# Sheet.net
KiCad netlist of a schematic drawn in Altium Designer
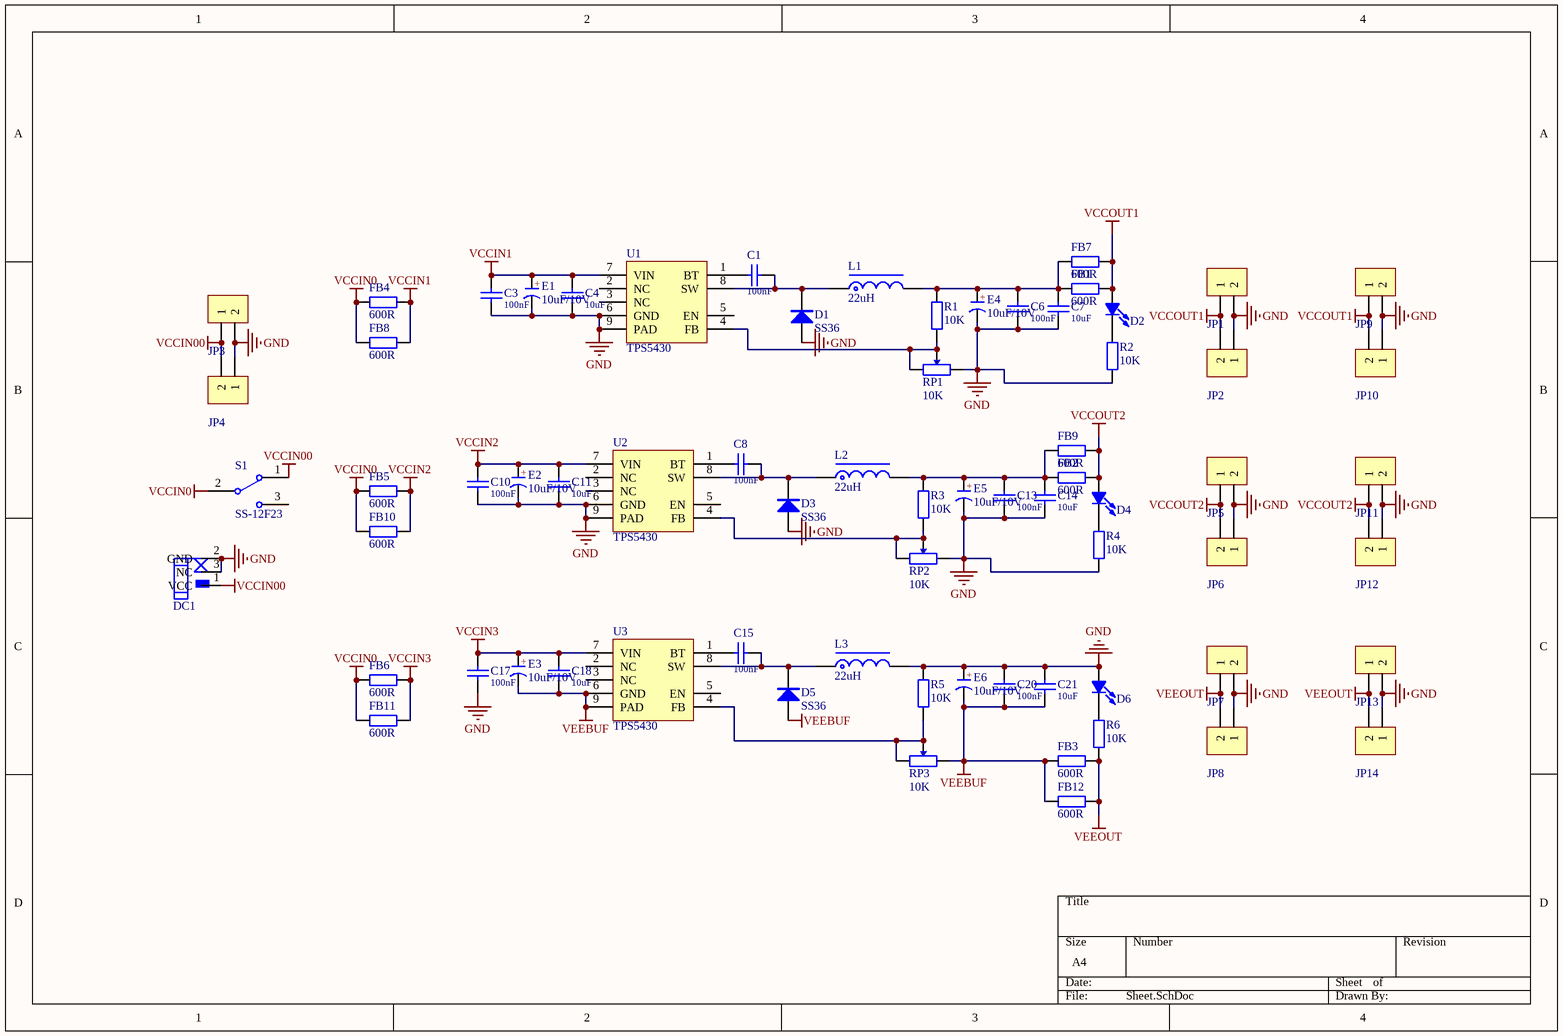
[diagram p0: Sheet.SchDoc]

(export (version "E")
  (design (tool "Eeschema 10.0.6"))
  (components
    (comp (ref "C1")
      (value "100nF")
      (footprint "C0603-L")
      (description "贴片瓷片电容")
      (fields (field (name "Comment") "Cap-S"))
      (libsource (lib "Library") (part "Cap-S"))
    )
    (comp (ref "C3")
      (value "100nF")
      (footprint "C0603-L")
      (description "贴片瓷片电容")
      (fields (field (name "Comment") "Cap-S"))
      (libsource (lib "Library") (part "Cap-S"))
    )
    (comp (ref "C4")
      (value "10uF")
      (footprint "C0603-L")
      (description "贴片瓷片电容")
      (fields (field (name "Comment") "Cap-S"))
      (libsource (lib "Library") (part "Cap-S"))
    )
    (comp (ref "C6")
      (value "100nF")
      (footprint "C0603-L")
      (description "贴片瓷片电容")
      (fields (field (name "Comment") "Cap-S"))
      (libsource (lib "Library") (part "Cap-S"))
    )
    (comp (ref "C7")
      (value "10uF")
      (footprint "C0603-L")
      (description "贴片瓷片电容")
      (fields (field (name "Comment") "Cap-S"))
      (libsource (lib "Library") (part "Cap-S"))
    )
    (comp (ref "C8")
      (value "100nF")
      (footprint "C0603-L")
      (description "贴片瓷片电容")
      (fields (field (name "Comment") "Cap-S"))
      (libsource (lib "Library") (part "Cap-S"))
    )
    (comp (ref "C10")
      (value "100nF")
      (footprint "C0603-L")
      (description "贴片瓷片电容")
      (fields (field (name "Comment") "Cap-S"))
      (libsource (lib "Library") (part "Cap-S"))
    )
    (comp (ref "C11")
      (value "10uF")
      (footprint "C0603-L")
      (description "贴片瓷片电容")
      (fields (field (name "Comment") "Cap-S"))
      (libsource (lib "Library") (part "Cap-S"))
    )
    (comp (ref "C13")
      (value "100nF")
      (footprint "C0603-L")
      (description "贴片瓷片电容")
      (fields (field (name "Comment") "Cap-S"))
      (libsource (lib "Library") (part "Cap-S"))
    )
    (comp (ref "C14")
      (value "10uF")
      (footprint "C0603-L")
      (description "贴片瓷片电容")
      (fields (field (name "Comment") "Cap-S"))
      (libsource (lib "Library") (part "Cap-S"))
    )
    (comp (ref "C15")
      (value "100nF")
      (footprint "C0603-L")
      (description "贴片瓷片电容")
      (fields (field (name "Comment") "Cap-S"))
      (libsource (lib "Library") (part "Cap-S"))
    )
    (comp (ref "C17")
      (value "100nF")
      (footprint "C0603-L")
      (description "贴片瓷片电容")
      (fields (field (name "Comment") "Cap-S"))
      (libsource (lib "Library") (part "Cap-S"))
    )
    (comp (ref "C18")
      (value "10uF")
      (footprint "C0603-L")
      (description "贴片瓷片电容")
      (fields (field (name "Comment") "Cap-S"))
      (libsource (lib "Library") (part "Cap-S"))
    )
    (comp (ref "C20")
      (value "100nF")
      (footprint "C0603-L")
      (description "贴片瓷片电容")
      (fields (field (name "Comment") "Cap-S"))
      (libsource (lib "Library") (part "Cap-S"))
    )
    (comp (ref "C21")
      (value "10uF")
      (footprint "C0603-L")
      (description "贴片瓷片电容")
      (fields (field (name "Comment") "Cap-S"))
      (libsource (lib "Library") (part "Cap-S"))
    )
    (comp (ref "D1")
      (value "SS36")
      (footprint "SMA")
      (description "整流二极管")
      (fields (field (name "版权归属") "源创客"))
      (libsource (lib "IL") (part "M7"))
    )
    (comp (ref "D2")
      (value "LED")
      (footprint "Led-0805_L")
      (description "发光二极管")
      (libsource (lib "Library") (part "LED"))
    )
    (comp (ref "D3")
      (value "SS36")
      (footprint "SMA")
      (description "整流二极管")
      (fields (field (name "版权归属") "源创客"))
      (libsource (lib "IL") (part "M7"))
    )
    (comp (ref "D4")
      (value "LED")
      (footprint "Led-0805_L")
      (description "发光二极管")
      (libsource (lib "Library") (part "LED"))
    )
    (comp (ref "D5")
      (value "SS36")
      (footprint "SMA")
      (description "整流二极管")
      (fields (field (name "版权归属") "源创客"))
      (libsource (lib "IL") (part "M7"))
    )
    (comp (ref "D6")
      (value "LED")
      (footprint "Led-0805_L")
      (description "发光二极管")
      (libsource (lib "Library") (part "LED"))
    )
    (comp (ref "DC1")
      (value "DC")
      (footprint "DCIN-L")
      (description "DC插座")
      (libsource (lib "Library") (part "DC"))
    )
    (comp (ref "E1")
      (value "10uF/10V")
      (footprint "CT 6*6 - V")
      (description "贴片固态电容")
      (fields (field (name "版权归属") "源创客"))
      (libsource (lib "IL") (part "C-CT"))
    )
    (comp (ref "E2")
      (value "10uF/10V")
      (footprint "CT 6*6 - V")
      (description "贴片固态电容")
      (fields (field (name "版权归属") "源创客"))
      (libsource (lib "IL") (part "C-CT"))
    )
    (comp (ref "E3")
      (value "10uF/10V")
      (footprint "CT 6*6 - V")
      (description "贴片固态电容")
      (fields (field (name "版权归属") "源创客"))
      (libsource (lib "IL") (part "C-CT"))
    )
    (comp (ref "E4")
      (value "10uF/10V")
      (footprint "CT 6*6 - V")
      (description "贴片固态电容")
      (fields (field (name "版权归属") "源创客"))
      (libsource (lib "IL") (part "C-CT"))
    )
    (comp (ref "E5")
      (value "10uF/10V")
      (footprint "CT 6*6 - V")
      (description "贴片固态电容")
      (fields (field (name "版权归属") "源创客"))
      (libsource (lib "IL") (part "C-CT"))
    )
    (comp (ref "E6")
      (value "10uF/10V")
      (footprint "CT 6*6 - V")
      (description "贴片固态电容")
      (fields (field (name "版权归属") "源创客"))
      (libsource (lib "IL") (part "C-CT"))
    )
    (comp (ref "FB1") (value "600R") (footprint "FB-0603") (libsource (lib "Library") (part "FB")))
    (comp (ref "FB2") (value "600R") (footprint "FB-0603") (libsource (lib "Library") (part "FB")))
    (comp (ref "FB3") (value "600R") (footprint "FB-0603") (libsource (lib "Library") (part "FB")))
    (comp (ref "FB4") (value "600R") (footprint "FB-0603") (libsource (lib "Library") (part "FB")))
    (comp (ref "FB5") (value "600R") (footprint "FB-0603") (libsource (lib "Library") (part "FB")))
    (comp (ref "FB6") (value "600R") (footprint "FB-0603") (libsource (lib "Library") (part "FB")))
    (comp (ref "FB7") (value "600R") (footprint "FB-0603") (libsource (lib "Library") (part "FB")))
    (comp (ref "FB8") (value "600R") (footprint "FB-0603") (libsource (lib "Library") (part "FB")))
    (comp (ref "FB9") (value "600R") (footprint "FB-0603") (libsource (lib "Library") (part "FB")))
    (comp (ref "FB10") (value "600R") (footprint "FB-0603") (libsource (lib "Library") (part "FB")))
    (comp (ref "FB11") (value "600R") (footprint "FB-0603") (libsource (lib "Library") (part "FB")))
    (comp (ref "FB12") (value "600R") (footprint "FB-0603") (libsource (lib "Library") (part "FB")))
    (comp (ref "JP1")
      (value "HDR-1X2")
      (footprint "VH3.96-LI-2P")
      (description "2P接插件")
      (fields (field (name "版权归属") "源创客"))
      (libsource (lib "") (part "Header 2_1_1"))
    )
    (comp (ref "JP2")
      (value "HDR-1X2")
      (footprint "VH3.96-LI-2P")
      (description "2P接插件")
      (fields (field (name "版权归属") "源创客"))
      (libsource (lib "IL") (part "Header 2_1"))
    )
    (comp (ref "JP3")
      (value "HDR-1X2")
      (footprint "VH3.96-LI-2P")
      (description "2P接插件")
      (fields (field (name "版权归属") "源创客"))
      (libsource (lib "") (part "Header 2_1_1"))
    )
    (comp (ref "JP4")
      (value "HDR-1X2")
      (footprint "VH3.96-LI-2P")
      (description "2P接插件")
      (fields (field (name "版权归属") "源创客"))
      (libsource (lib "IL") (part "Header 2_1"))
    )
    (comp (ref "JP5")
      (value "HDR-1X2")
      (footprint "VH3.96-LI-2P")
      (description "2P接插件")
      (fields (field (name "版权归属") "源创客"))
      (libsource (lib "") (part "Header 2_1_1"))
    )
    (comp (ref "JP6")
      (value "HDR-1X2")
      (footprint "VH3.96-LI-2P")
      (description "2P接插件")
      (fields (field (name "版权归属") "源创客"))
      (libsource (lib "IL") (part "Header 2_1"))
    )
    (comp (ref "JP7")
      (value "HDR-1X2")
      (footprint "VH3.96-LI-2P")
      (description "2P接插件")
      (fields (field (name "版权归属") "源创客"))
      (libsource (lib "") (part "Header 2_1_1"))
    )
    (comp (ref "JP8")
      (value "HDR-1X2")
      (footprint "VH3.96-LI-2P")
      (description "2P接插件")
      (fields (field (name "版权归属") "源创客"))
      (libsource (lib "IL") (part "Header 2_1"))
    )
    (comp (ref "JP9")
      (value "HDR-1X2")
      (footprint "VH3.96-LI-2P")
      (description "2P接插件")
      (fields (field (name "版权归属") "源创客"))
      (libsource (lib "") (part "Header 2_1_1"))
    )
    (comp (ref "JP10")
      (value "HDR-1X2")
      (footprint "VH3.96-LI-2P")
      (description "2P接插件")
      (fields (field (name "版权归属") "源创客"))
      (libsource (lib "IL") (part "Header 2_1"))
    )
    (comp (ref "JP11")
      (value "HDR-1X2")
      (footprint "VH3.96-LI-2P")
      (description "2P接插件")
      (fields (field (name "版权归属") "源创客"))
      (libsource (lib "") (part "Header 2_1_1"))
    )
    (comp (ref "JP12")
      (value "HDR-1X2")
      (footprint "VH3.96-LI-2P")
      (description "2P接插件")
      (fields (field (name "版权归属") "源创客"))
      (libsource (lib "IL") (part "Header 2_1"))
    )
    (comp (ref "JP13")
      (value "HDR-1X2")
      (footprint "VH3.96-LI-2P")
      (description "2P接插件")
      (fields (field (name "版权归属") "源创客"))
      (libsource (lib "") (part "Header 2_1_1"))
    )
    (comp (ref "JP14")
      (value "HDR-1X2")
      (footprint "VH3.96-LI-2P")
      (description "2P接插件")
      (fields (field (name "版权归属") "源创客"))
      (libsource (lib "IL") (part "Header 2_1"))
    )
    (comp (ref "L1")
      (value "22uH")
      (footprint "CDRH73")
      (description "功率屏蔽电感")
      (fields (field (name "版权归属") "源创客"))
      (libsource (lib "IL") (part "L-CDRH"))
    )
    (comp (ref "L2")
      (value "22uH")
      (footprint "CDRH73")
      (description "功率屏蔽电感")
      (fields (field (name "版权归属") "源创客"))
      (libsource (lib "IL") (part "L-CDRH"))
    )
    (comp (ref "L3")
      (value "22uH")
      (footprint "CDRH73")
      (description "功率屏蔽电感")
      (fields (field (name "版权归属") "源创客"))
      (libsource (lib "IL") (part "L-CDRH"))
    )
    (comp (ref "R1")
      (value "10K")
      (footprint "R 0603_L")
      (description "贴片电阻")
      (fields (field (name "版权归属") "源创客"))
      (libsource (lib "IL") (part "R"))
    )
    (comp (ref "R2")
      (value "10K")
      (footprint "R 0603_L")
      (description "贴片电阻")
      (fields (field (name "版权归属") "源创客"))
      (libsource (lib "IL") (part "R"))
    )
    (comp (ref "R3")
      (value "10K")
      (footprint "R 0603_L")
      (description "贴片电阻")
      (fields (field (name "版权归属") "源创客"))
      (libsource (lib "IL") (part "R"))
    )
    (comp (ref "R4")
      (value "10K")
      (footprint "R 0603_L")
      (description "贴片电阻")
      (fields (field (name "版权归属") "源创客"))
      (libsource (lib "IL") (part "R"))
    )
    (comp (ref "R5")
      (value "10K")
      (footprint "R 0603_L")
      (description "贴片电阻")
      (fields (field (name "版权归属") "源创客"))
      (libsource (lib "IL") (part "R"))
    )
    (comp (ref "R6")
      (value "10K")
      (footprint "R 0603_L")
      (description "贴片电阻")
      (fields (field (name "版权归属") "源创客"))
      (libsource (lib "IL") (part "R"))
    )
    (comp (ref "RP1")
      (value "10K")
      (footprint "3296W")
      (description "插件单联电位器")
      (fields (field (name "版权归属") "源创客"))
      (libsource (lib "IL") (part "RP-ID"))
    )
    (comp (ref "RP2")
      (value "10K")
      (footprint "3296W")
      (description "插件单联电位器")
      (fields (field (name "版权归属") "源创客"))
      (libsource (lib "IL") (part "RP-ID"))
    )
    (comp (ref "RP3")
      (value "10K")
      (footprint "3296W")
      (description "插件单联电位器")
      (fields (field (name "版权归属") "源创客"))
      (libsource (lib "IL") (part "RP-ID"))
    )
    (comp (ref "S1")
      (value "SS-12F23")
      (footprint "SS-12D10")
      (description "1路波动开关")
      (fields (field (name "版权归属") "源创客"))
      (libsource (lib "IL") (part "SSW-1P"))
    )
    (comp (ref "U1")
      (value "TPS5430")
      (footprint "SOP-8 with pad")
      (libsource (lib "Library") (part "TPS5430"))
    )
    (comp (ref "U2")
      (value "TPS5430")
      (footprint "SOP-8 with pad")
      (libsource (lib "Library") (part "TPS5430"))
    )
    (comp (ref "U3")
      (value "TPS5430")
      (footprint "SOP-8 with pad")
      (libsource (lib "Library") (part "TPS5430"))
    )
  )
  (nets
    (net (code "1") (name "GND") (class "Default")
      (node (ref "C10") (pin "1") (pinfunction "1_1") (pintype "passive"))
      (node (ref "C11") (pin "1") (pinfunction "1_1") (pintype "passive"))
      (node (ref "C13") (pin "1") (pinfunction "1_1") (pintype "passive"))
      (node (ref "C14") (pin "1") (pinfunction "1_1") (pintype "passive"))
      (node (ref "C17") (pin "1") (pinfunction "1_1") (pintype "passive"))
      (node (ref "C20") (pin "2") (pinfunction "2_2") (pintype "passive"))
      (node (ref "C21") (pin "2") (pinfunction "2_2") (pintype "passive"))
      (node (ref "C3") (pin "1") (pinfunction "1_1") (pintype "passive"))
      (node (ref "C4") (pin "1") (pinfunction "1_1") (pintype "passive"))
      (node (ref "C6") (pin "1") (pinfunction "1_1") (pintype "passive"))
      (node (ref "C7") (pin "1") (pinfunction "1_1") (pintype "passive"))
      (node (ref "D1") (pin "1") (pinfunction "A_1") (pintype "passive"))
      (node (ref "D3") (pin "1") (pinfunction "A_1") (pintype "passive"))
      (node (ref "D6") (pin "1") (pinfunction "1_1") (pintype "passive"))
      (node (ref "DC1") (pin "2") (pinfunction "GND_2") (pintype "open_collector"))
      (node (ref "DC1") (pin "3") (pinfunction "NC_3") (pintype "open_collector"))
      (node (ref "E1") (pin "2") (pinfunction "K_2") (pintype "passive"))
      (node (ref "E2") (pin "2") (pinfunction "K_2") (pintype "passive"))
      (node (ref "E4") (pin "2") (pinfunction "K_2") (pintype "passive"))
      (node (ref "E5") (pin "2") (pinfunction "K_2") (pintype "passive"))
      (node (ref "E6") (pin "1") (pinfunction "A_1") (pintype "passive"))
      (node (ref "JP1") (pin "2") (pinfunction "2_2") (pintype "passive"))
      (node (ref "JP10") (pin "1") (pinfunction "1_1") (pintype "passive"))
      (node (ref "JP11") (pin "2") (pinfunction "2_2") (pintype "passive"))
      (node (ref "JP12") (pin "1") (pinfunction "1_1") (pintype "passive"))
      (node (ref "JP13") (pin "2") (pinfunction "2_2") (pintype "passive"))
      (node (ref "JP14") (pin "1") (pinfunction "1_1") (pintype "passive"))
      (node (ref "JP2") (pin "1") (pinfunction "1_1") (pintype "passive"))
      (node (ref "JP3") (pin "2") (pinfunction "2_2") (pintype "passive"))
      (node (ref "JP4") (pin "1") (pinfunction "1_1") (pintype "passive"))
      (node (ref "JP5") (pin "2") (pinfunction "2_2") (pintype "passive"))
      (node (ref "JP6") (pin "1") (pinfunction "1_1") (pintype "passive"))
      (node (ref "JP7") (pin "2") (pinfunction "2_2") (pintype "passive"))
      (node (ref "JP8") (pin "1") (pinfunction "1_1") (pintype "passive"))
      (node (ref "JP9") (pin "2") (pinfunction "2_2") (pintype "passive"))
      (node (ref "L3") (pin "2") (pinfunction "2_2") (pintype "passive"))
      (node (ref "R2") (pin "1") (pinfunction "1_1") (pintype "passive"))
      (node (ref "R4") (pin "1") (pinfunction "1_1") (pintype "passive"))
      (node (ref "R5") (pin "2") (pinfunction "2_2") (pintype "passive"))
      (node (ref "RP1") (pin "3") (pinfunction "3_3") (pintype "passive"))
      (node (ref "RP2") (pin "3") (pinfunction "3_3") (pintype "passive"))
      (node (ref "U1") (pin "6") (pinfunction "GND_6") (pintype "passive"))
      (node (ref "U1") (pin "9") (pinfunction "PAD_9") (pintype "passive"))
      (node (ref "U2") (pin "6") (pinfunction "GND_6") (pintype "passive"))
      (node (ref "U2") (pin "9") (pinfunction "PAD_9") (pintype "passive"))
    )
    (net (code "2") (name "Net-(D1-K)") (class "Default")
      (node (ref "C1") (pin "2") (pinfunction "2_2") (pintype "passive"))
      (node (ref "D1") (pin "2") (pinfunction "K_2") (pintype "passive"))
      (node (ref "L1") (pin "1") (pinfunction "1_1") (pintype "passive"))
      (node (ref "U1") (pin "8") (pinfunction "SW_8") (pintype "passive"))
    )
    (net (code "3") (name "Net-(D2-Pad2)") (class "Default")
      (node (ref "D2") (pin "2") (pinfunction "2_2") (pintype "passive"))
      (node (ref "R2") (pin "2") (pinfunction "2_2") (pintype "passive"))
    )
    (net (code "4") (name "Net-(D3-K)") (class "Default")
      (node (ref "C8") (pin "2") (pinfunction "2_2") (pintype "passive"))
      (node (ref "D3") (pin "2") (pinfunction "K_2") (pintype "passive"))
      (node (ref "L2") (pin "1") (pinfunction "1_1") (pintype "passive"))
      (node (ref "U2") (pin "8") (pinfunction "SW_8") (pintype "passive"))
    )
    (net (code "5") (name "Net-(D4-Pad2)") (class "Default")
      (node (ref "D4") (pin "2") (pinfunction "2_2") (pintype "passive"))
      (node (ref "R4") (pin "2") (pinfunction "2_2") (pintype "passive"))
    )
    (net (code "6") (name "Net-(D5-K)") (class "Default")
      (node (ref "C15") (pin "2") (pinfunction "2_2") (pintype "passive"))
      (node (ref "D5") (pin "2") (pinfunction "K_2") (pintype "passive"))
      (node (ref "L3") (pin "1") (pinfunction "1_1") (pintype "passive"))
      (node (ref "U3") (pin "8") (pinfunction "SW_8") (pintype "passive"))
    )
    (net (code "7") (name "Net-(D6-Pad2)") (class "Default")
      (node (ref "D6") (pin "2") (pinfunction "2_2") (pintype "passive"))
      (node (ref "R6") (pin "2") (pinfunction "2_2") (pintype "passive"))
    )
    (net (code "8") (name "Net-(E4-A)") (class "Default")
      (node (ref "C6") (pin "2") (pinfunction "2_2") (pintype "passive"))
      (node (ref "C7") (pin "2") (pinfunction "2_2") (pintype "passive"))
      (node (ref "E4") (pin "1") (pinfunction "A_1") (pintype "passive"))
      (node (ref "FB1") (pin "1") (pinfunction "1_1") (pintype "passive"))
      (node (ref "FB7") (pin "1") (pinfunction "1_1") (pintype "passive"))
      (node (ref "L1") (pin "2") (pinfunction "2_2") (pintype "passive"))
      (node (ref "R1") (pin "2") (pinfunction "2_2") (pintype "passive"))
    )
    (net (code "9") (name "Net-(E5-A)") (class "Default")
      (node (ref "C13") (pin "2") (pinfunction "2_2") (pintype "passive"))
      (node (ref "C14") (pin "2") (pinfunction "2_2") (pintype "passive"))
      (node (ref "E5") (pin "1") (pinfunction "A_1") (pintype "passive"))
      (node (ref "FB2") (pin "1") (pinfunction "1_1") (pintype "passive"))
      (node (ref "FB9") (pin "1") (pinfunction "1_1") (pintype "passive"))
      (node (ref "L2") (pin "2") (pinfunction "2_2") (pintype "passive"))
      (node (ref "R3") (pin "2") (pinfunction "2_2") (pintype "passive"))
    )
    (net (code "10") (name "Net-(U1-BT)") (class "Default")
      (node (ref "C1") (pin "1") (pinfunction "1_1") (pintype "passive"))
      (node (ref "U1") (pin "1") (pinfunction "BT_1") (pintype "passive"))
    )
    (net (code "11") (name "Net-(U1-FB)") (class "Default")
      (node (ref "R1") (pin "1") (pinfunction "1_1") (pintype "passive"))
      (node (ref "RP1") (pin "1") (pinfunction "1_1") (pintype "passive"))
      (node (ref "RP1") (pin "2") (pinfunction "2_2") (pintype "passive"))
      (node (ref "U1") (pin "4") (pinfunction "FB_4") (pintype "passive"))
    )
    (net (code "12") (name "Net-(U2-BT)") (class "Default")
      (node (ref "C8") (pin "1") (pinfunction "1_1") (pintype "passive"))
      (node (ref "U2") (pin "1") (pinfunction "BT_1") (pintype "passive"))
    )
    (net (code "13") (name "Net-(U2-FB)") (class "Default")
      (node (ref "R3") (pin "1") (pinfunction "1_1") (pintype "passive"))
      (node (ref "RP2") (pin "1") (pinfunction "1_1") (pintype "passive"))
      (node (ref "RP2") (pin "2") (pinfunction "2_2") (pintype "passive"))
      (node (ref "U2") (pin "4") (pinfunction "FB_4") (pintype "passive"))
    )
    (net (code "14") (name "Net-(U3-BT)") (class "Default")
      (node (ref "C15") (pin "1") (pinfunction "1_1") (pintype "passive"))
      (node (ref "U3") (pin "1") (pinfunction "BT_1") (pintype "passive"))
    )
    (net (code "15") (name "Net-(U3-FB)") (class "Default")
      (node (ref "R5") (pin "1") (pinfunction "1_1") (pintype "passive"))
      (node (ref "RP3") (pin "1") (pinfunction "1_1") (pintype "passive"))
      (node (ref "RP3") (pin "2") (pinfunction "2_2") (pintype "passive"))
      (node (ref "U3") (pin "4") (pinfunction "FB_4") (pintype "passive"))
    )
    (net (code "16") (name "VCCIN00") (class "Default")
      (node (ref "DC1") (pin "1") (pinfunction "VCC_1") (pintype "open_collector"))
      (node (ref "JP3") (pin "1") (pinfunction "1_1") (pintype "passive"))
      (node (ref "JP4") (pin "2") (pinfunction "2_2") (pintype "passive"))
      (node (ref "S1") (pin "1") (pinfunction "1_1") (pintype "passive"))
    )
    (net (code "17") (name "VCCIN0") (class "Default")
      (node (ref "FB10") (pin "1") (pinfunction "1_1") (pintype "passive"))
      (node (ref "FB11") (pin "1") (pinfunction "1_1") (pintype "passive"))
      (node (ref "FB4") (pin "1") (pinfunction "1_1") (pintype "passive"))
      (node (ref "FB5") (pin "1") (pinfunction "1_1") (pintype "passive"))
      (node (ref "FB6") (pin "1") (pinfunction "1_1") (pintype "passive"))
      (node (ref "FB8") (pin "1") (pinfunction "1_1") (pintype "passive"))
      (node (ref "S1") (pin "2") (pinfunction "2_2") (pintype "passive"))
    )
    (net (code "18") (name "VCCIN1") (class "Default")
      (node (ref "C3") (pin "2") (pinfunction "2_2") (pintype "passive"))
      (node (ref "C4") (pin "2") (pinfunction "2_2") (pintype "passive"))
      (node (ref "E1") (pin "1") (pinfunction "A_1") (pintype "passive"))
      (node (ref "FB4") (pin "2") (pinfunction "2_2") (pintype "passive"))
      (node (ref "FB8") (pin "2") (pinfunction "2_2") (pintype "passive"))
      (node (ref "U1") (pin "7") (pinfunction "VIN_7") (pintype "passive"))
    )
    (net (code "19") (name "VCCIN2") (class "Default")
      (node (ref "C10") (pin "2") (pinfunction "2_2") (pintype "passive"))
      (node (ref "C11") (pin "2") (pinfunction "2_2") (pintype "passive"))
      (node (ref "E2") (pin "1") (pinfunction "A_1") (pintype "passive"))
      (node (ref "FB10") (pin "2") (pinfunction "2_2") (pintype "passive"))
      (node (ref "FB5") (pin "2") (pinfunction "2_2") (pintype "passive"))
      (node (ref "U2") (pin "7") (pinfunction "VIN_7") (pintype "passive"))
    )
    (net (code "20") (name "VCCIN3") (class "Default")
      (node (ref "C17") (pin "2") (pinfunction "2_2") (pintype "passive"))
      (node (ref "C18") (pin "2") (pinfunction "2_2") (pintype "passive"))
      (node (ref "E3") (pin "1") (pinfunction "A_1") (pintype "passive"))
      (node (ref "FB11") (pin "2") (pinfunction "2_2") (pintype "passive"))
      (node (ref "FB6") (pin "2") (pinfunction "2_2") (pintype "passive"))
      (node (ref "U3") (pin "7") (pinfunction "VIN_7") (pintype "passive"))
    )
    (net (code "21") (name "VCCOUT1") (class "Default")
      (node (ref "D2") (pin "1") (pinfunction "1_1") (pintype "passive"))
      (node (ref "FB1") (pin "2") (pinfunction "2_2") (pintype "passive"))
      (node (ref "FB7") (pin "2") (pinfunction "2_2") (pintype "passive"))
      (node (ref "JP1") (pin "1") (pinfunction "1_1") (pintype "passive"))
      (node (ref "JP10") (pin "2") (pinfunction "2_2") (pintype "passive"))
      (node (ref "JP2") (pin "2") (pinfunction "2_2") (pintype "passive"))
      (node (ref "JP9") (pin "1") (pinfunction "1_1") (pintype "passive"))
    )
    (net (code "22") (name "VCCOUT2") (class "Default")
      (node (ref "D4") (pin "1") (pinfunction "1_1") (pintype "passive"))
      (node (ref "FB2") (pin "2") (pinfunction "2_2") (pintype "passive"))
      (node (ref "FB9") (pin "2") (pinfunction "2_2") (pintype "passive"))
      (node (ref "JP11") (pin "1") (pinfunction "1_1") (pintype "passive"))
      (node (ref "JP12") (pin "2") (pinfunction "2_2") (pintype "passive"))
      (node (ref "JP5") (pin "1") (pinfunction "1_1") (pintype "passive"))
      (node (ref "JP6") (pin "2") (pinfunction "2_2") (pintype "passive"))
    )
    (net (code "23") (name "VEEBUF") (class "Default")
      (node (ref "C18") (pin "1") (pinfunction "1_1") (pintype "passive"))
      (node (ref "C20") (pin "1") (pinfunction "1_1") (pintype "passive"))
      (node (ref "C21") (pin "1") (pinfunction "1_1") (pintype "passive"))
      (node (ref "D5") (pin "1") (pinfunction "A_1") (pintype "passive"))
      (node (ref "E3") (pin "2") (pinfunction "K_2") (pintype "passive"))
      (node (ref "E6") (pin "2") (pinfunction "K_2") (pintype "passive"))
      (node (ref "FB12") (pin "1") (pinfunction "1_1") (pintype "passive"))
      (node (ref "FB3") (pin "1") (pinfunction "1_1") (pintype "passive"))
      (node (ref "RP3") (pin "3") (pinfunction "3_3") (pintype "passive"))
      (node (ref "U3") (pin "6") (pinfunction "GND_6") (pintype "passive"))
      (node (ref "U3") (pin "9") (pinfunction "PAD_9") (pintype "passive"))
    )
    (net (code "24") (name "VEEOUT") (class "Default")
      (node (ref "FB12") (pin "2") (pinfunction "2_2") (pintype "passive"))
      (node (ref "FB3") (pin "2") (pinfunction "2_2") (pintype "passive"))
      (node (ref "JP13") (pin "1") (pinfunction "1_1") (pintype "passive"))
      (node (ref "JP14") (pin "2") (pinfunction "2_2") (pintype "passive"))
      (node (ref "JP7") (pin "1") (pinfunction "1_1") (pintype "passive"))
      (node (ref "JP8") (pin "2") (pinfunction "2_2") (pintype "passive"))
      (node (ref "R6") (pin "1") (pinfunction "1_1") (pintype "passive"))
    )
    (net (code "25") (name "unconnected-(S1-Pad3)") (class "Default")
      (node (ref "S1") (pin "3") (pinfunction "3_3") (pintype "passive"))
    )
    (net (code "26") (name "unconnected-(U1-EN-Pad5)") (class "Default")
      (node (ref "U1") (pin "5") (pinfunction "EN_5") (pintype "passive"))
    )
    (net (code "27") (name "unconnected-(U1-NC-Pad2)") (class "Default")
      (node (ref "U1") (pin "2") (pinfunction "NC_2") (pintype "passive"))
    )
    (net (code "28") (name "unconnected-(U1-NC-Pad3)") (class "Default")
      (node (ref "U1") (pin "3") (pinfunction "NC_3") (pintype "passive"))
    )
    (net (code "29") (name "unconnected-(U2-EN-Pad5)") (class "Default")
      (node (ref "U2") (pin "5") (pinfunction "EN_5") (pintype "passive"))
    )
    (net (code "30") (name "unconnected-(U2-NC-Pad2)") (class "Default")
      (node (ref "U2") (pin "2") (pinfunction "NC_2") (pintype "passive"))
    )
    (net (code "31") (name "unconnected-(U2-NC-Pad3)") (class "Default")
      (node (ref "U2") (pin "3") (pinfunction "NC_3") (pintype "passive"))
    )
    (net (code "32") (name "unconnected-(U3-EN-Pad5)") (class "Default")
      (node (ref "U3") (pin "5") (pinfunction "EN_5") (pintype "passive"))
    )
    (net (code "33") (name "unconnected-(U3-NC-Pad2)") (class "Default")
      (node (ref "U3") (pin "2") (pinfunction "NC_2") (pintype "passive"))
    )
    (net (code "34") (name "unconnected-(U3-NC-Pad3)") (class "Default")
      (node (ref "U3") (pin "3") (pinfunction "NC_3") (pintype "passive"))
    )
  )
)
